# YarnControl_Driver_v1_3.net
KiCad netlist of a schematic drawn in Altium Designer
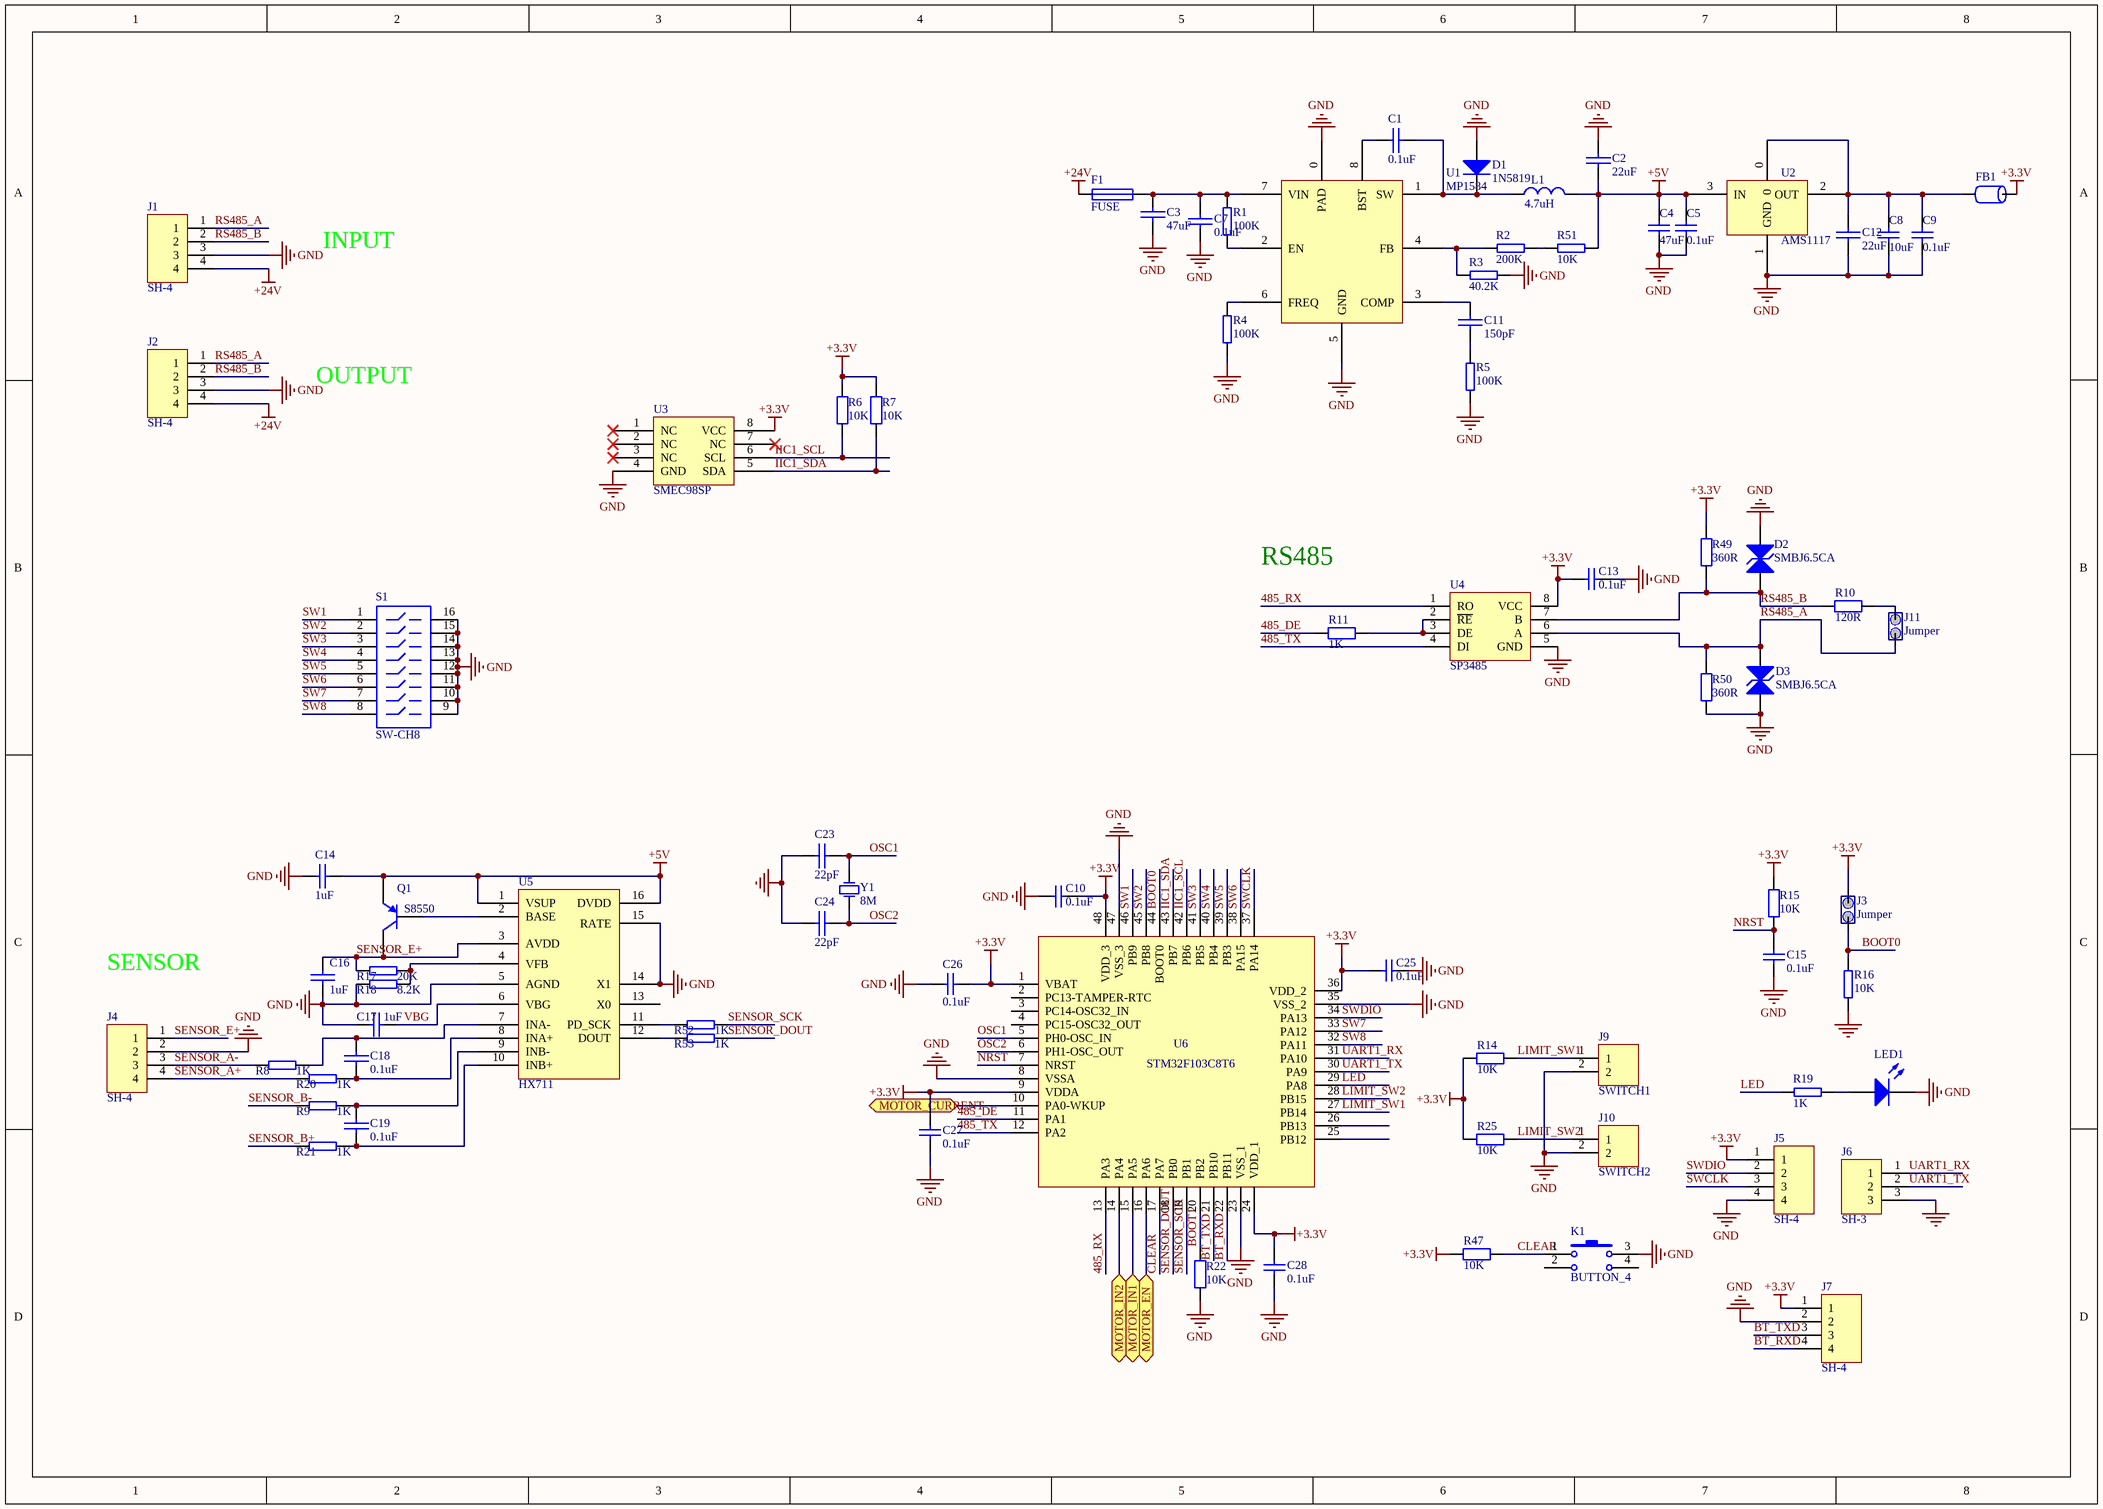
[diagram p0: YarnControl_Driver_v1.3.SchDoc]

(export (version "E")
  (design (tool "Eeschema 10.0.6"))
  (components
    (comp (ref "C1")
      (value "0.1uF")
      (footprint "0805")
      (description "电容")
      (libsource (lib "Component") (part "CAP"))
    )
    (comp (ref "C2")
      (value "22uF")
      (footprint "1206")
      (description "电容")
      (libsource (lib "Component") (part "CAP"))
    )
    (comp (ref "C3")
      (value "47uF")
      (footprint "1812")
      (description "电容")
      (libsource (lib "Component") (part "CAP"))
    )
    (comp (ref "C4") (value "47uF") (footprint "1210") (libsource (lib "Componet") (part "Cap0805")))
    (comp (ref "C5") (value "0.1uF") (footprint "0805") (libsource (lib "Componet") (part "Cap0805")))
    (comp (ref "C7")
      (value "0.1uF")
      (footprint "0805")
      (description "电容")
      (libsource (lib "Component") (part "CAP"))
    )
    (comp (ref "C8") (value "10uF") (footprint "0805") (libsource (lib "Componet") (part "Cap0805")))
    (comp (ref "C9") (value "0.1uF") (footprint "0805") (libsource (lib "Componet") (part "Cap0805")))
    (comp (ref "C10")
      (value "0.1uF")
      (footprint "0805")
      (description "Capacitor")
      (fields (field (name "PUBLISHER") "Altium Limited"))
      (libsource (lib "TIAN's Schlib") (part "Cap"))
    )
    (comp (ref "C11")
      (value "150pF")
      (footprint "0805")
      (description "电容")
      (libsource (lib "Component") (part "CAP"))
    )
    (comp (ref "C12")
      (value "22uF")
      (footprint "1206")
      (description "电容")
      (libsource (lib "Component") (part "CAP"))
    )
    (comp (ref "C13")
      (value "0.1uF")
      (footprint "0805")
      (description "Capacitor")
      (fields (field (name "PUBLISHER") "Altium Limited"))
      (libsource (lib "TIAN's Schlib") (part "Cap"))
    )
    (comp (ref "C14")
      (value "1uF")
      (footprint "0805")
      (description "电容")
      (libsource (lib "Component") (part "CAP"))
    )
    (comp (ref "C15")
      (value "0.1uF")
      (footprint "0805")
      (description "Capacitor")
      (fields (field (name "PUBLISHER") "Altium Limited"))
      (libsource (lib "TIAN's Schlib") (part "Cap"))
    )
    (comp (ref "C16")
      (value "1uF")
      (footprint "0805")
      (description "电容")
      (libsource (lib "Component") (part "CAP"))
    )
    (comp (ref "C17")
      (value "1uF")
      (footprint "0805")
      (description "电容")
      (libsource (lib "Component") (part "CAP"))
    )
    (comp (ref "C18")
      (value "0.1uF")
      (footprint "0805")
      (description "电容")
      (libsource (lib "Component") (part "CAP"))
    )
    (comp (ref "C19")
      (value "0.1uF")
      (footprint "0805")
      (description "电容")
      (libsource (lib "Component") (part "CAP"))
    )
    (comp (ref "C23")
      (value "22pF")
      (footprint "0805")
      (description "电容")
      (libsource (lib "Component") (part "CAP"))
    )
    (comp (ref "C24")
      (value "22pF")
      (footprint "0805")
      (description "电容")
      (libsource (lib "Component") (part "CAP"))
    )
    (comp (ref "C25")
      (value "0.1uF")
      (footprint "0805")
      (description "Capacitor")
      (fields (field (name "PUBLISHER") "Altium Limited"))
      (libsource (lib "TIAN's Schlib") (part "Cap"))
    )
    (comp (ref "C26")
      (value "0.1uF")
      (footprint "0805")
      (description "Capacitor")
      (fields (field (name "PUBLISHER") "Altium Limited"))
      (libsource (lib "TIAN's Schlib") (part "Cap"))
    )
    (comp (ref "C27")
      (value "0.1uF")
      (footprint "0805")
      (description "Capacitor")
      (fields (field (name "PUBLISHER") "Altium Limited"))
      (libsource (lib "TIAN's Schlib") (part "Cap"))
    )
    (comp (ref "C28")
      (value "0.1uF")
      (footprint "0805")
      (description "Capacitor")
      (fields (field (name "PUBLISHER") "Altium Limited"))
      (libsource (lib "TIAN's Schlib") (part "Cap"))
    )
    (comp (ref "D1")
      (value "1N5819")
      (footprint "Diode_TP2")
      (description "二极管")
      (fields (field (name "PUBLISHER") "Altium Limited"))
      (libsource (lib "Component") (part "Diode"))
    )
    (comp (ref "D2")
      (value "SMBJ6.5CA")
      (footprint "SMBJ_DO-214")
      (fields (field (name "PUBLISHER") "Altium Limited"))
      (libsource (lib "TIAN's Schlib") (part "TVS"))
    )
    (comp (ref "D3")
      (value "SMBJ6.5CA")
      (footprint "SMBJ_DO-214")
      (fields (field (name "PUBLISHER") "Altium Limited"))
      (libsource (lib "TIAN's Schlib") (part "TVS"))
    )
    (comp (ref "F1")
      (value "FUSE")
      (footprint "1206")
      (description "保险丝")
      (libsource (lib "Component") (part "FUSE"))
    )
    (comp (ref "FB1") (value "FERRITE") (footprint "0805") (libsource (lib "Connector") (part "FERRITE")))
    (comp (ref "J1") (value "SH-4") (footprint "J381-4-90") (libsource (lib "") (part "SH-4_1")))
    (comp (ref "J2") (value "SH-4") (footprint "J381-4-90") (libsource (lib "") (part "SH-4_1")))
    (comp (ref "J3") (value "Jumper") (footprint "J254-2") (libsource (lib "Connector") (part "Jumper")))
    (comp (ref "J4") (value "SH-4") (footprint "KF2510-4") (libsource (lib "") (part "SH-4_1")))
    (comp (ref "J5") (value "SH-4") (footprint "J254-4") (libsource (lib "Connector") (part "SH-4")))
    (comp (ref "J6") (value "SH-3") (footprint "J2.54-3") (libsource (lib "Connector") (part "SH-3")))
    (comp (ref "J7") (value "SH-4") (footprint "J254-4") (libsource (lib "Connector") (part "SH-4")))
    (comp (ref "J9") (value "SWITCH1") (footprint "XH2.54-2T") (libsource (lib "Connector") (part "SH-2")))
    (comp (ref "J10") (value "SWITCH2") (footprint "XH2.54-2T") (libsource (lib "Connector") (part "SH-2")))
    (comp (ref "J11") (value "Jumper") (footprint "J254-2") (libsource (lib "Connector") (part "Jumper")))
    (comp (ref "K1") (value "BUTTON_4") (footprint "Button1") (libsource (lib "Componet") (part "BUTTON_4")))
    (comp (ref "L1")
      (value "4.7uH")
      (footprint "Inductance6*6")
      (description "电感")
      (libsource (lib "Component") (part "Inductor"))
    )
    (comp (ref "LED1")
      (value "GREEN")
      (footprint "LED")
      (description "Typical RED, GREEN, YELLOW, AMBER GaAs LED")
      (fields (field (name "PUBLISHER") "Altium Limited"))
      (libsource (lib "Miscellaneous Devices") (part "LED2"))
    )
    (comp (ref "Q1") (value "S8550") (footprint "901X_SOT-23") (libsource (lib "Componet") (part "PNP")))
    (comp (ref "R1")
      (value "100K")
      (footprint "0805")
      (description "电阻")
      (libsource (lib "Component") (part "RES"))
    )
    (comp (ref "R2")
      (value "200K")
      (footprint "0805")
      (description "电阻")
      (libsource (lib "Component") (part "RES"))
    )
    (comp (ref "R3")
      (value "40.2K")
      (footprint "0805")
      (description "电阻")
      (libsource (lib "Component") (part "RES"))
    )
    (comp (ref "R4")
      (value "100K")
      (footprint "0805")
      (description "电阻")
      (libsource (lib "Component") (part "RES"))
    )
    (comp (ref "R5")
      (value "100K")
      (footprint "0805")
      (description "电阻")
      (libsource (lib "Component") (part "RES"))
    )
    (comp (ref "R6")
      (value "10K")
      (footprint "0805")
      (description "Resistor")
      (fields (field (name "PUBLISHER") "Altium Limited"))
      (libsource (lib "") (part "Res2_2"))
    )
    (comp (ref "R7")
      (value "10K")
      (footprint "0805")
      (description "Resistor")
      (fields (field (name "PUBLISHER") "Altium Limited"))
      (libsource (lib "") (part "Res2_2"))
    )
    (comp (ref "R8")
      (value "1K")
      (footprint "0805")
      (description "电阻")
      (libsource (lib "Component") (part "RES"))
    )
    (comp (ref "R9")
      (value "1K")
      (footprint "0805")
      (description "电阻")
      (libsource (lib "Component") (part "RES"))
    )
    (comp (ref "R10")
      (value "120R")
      (footprint "0805")
      (description "Resistor")
      (fields (field (name "PUBLISHER") "Altium Limited"))
      (libsource (lib "TIAN's Schlib") (part "Res2"))
    )
    (comp (ref "R11")
      (value "1K")
      (footprint "0805")
      (description "Resistor")
      (fields (field (name "PUBLISHER") "Altium Limited"))
      (libsource (lib "") (part "Res2_1"))
    )
    (comp (ref "R14")
      (value "10K")
      (footprint "0805")
      (description "Resistor")
      (fields (field (name "PUBLISHER") "Altium Limited"))
      (libsource (lib "") (part "Res2_1"))
    )
    (comp (ref "R15")
      (value "10K")
      (footprint "0805")
      (description "Resistor")
      (fields (field (name "PUBLISHER") "Altium Limited"))
      (libsource (lib "") (part "Res2_2"))
    )
    (comp (ref "R16")
      (value "10K")
      (footprint "0805")
      (description "电阻")
      (libsource (lib "Component") (part "RES"))
    )
    (comp (ref "R17")
      (value "20K")
      (footprint "0805")
      (description "电阻")
      (libsource (lib "Component") (part "RES"))
    )
    (comp (ref "R18")
      (value "8.2K")
      (footprint "0805")
      (description "电阻")
      (libsource (lib "Component") (part "RES"))
    )
    (comp (ref "R19")
      (value "1K")
      (footprint "0805")
      (description "电阻")
      (libsource (lib "Component") (part "RES"))
    )
    (comp (ref "R20")
      (value "1K")
      (footprint "0805")
      (description "电阻")
      (libsource (lib "Component") (part "RES"))
    )
    (comp (ref "R21")
      (value "1K")
      (footprint "0805")
      (description "电阻")
      (libsource (lib "Component") (part "RES"))
    )
    (comp (ref "R22")
      (value "10K")
      (footprint "0805")
      (description "Resistor")
      (fields (field (name "PUBLISHER") "Altium Limited"))
      (libsource (lib "") (part "Res2_2"))
    )
    (comp (ref "R25")
      (value "10K")
      (footprint "0805")
      (description "Resistor")
      (fields (field (name "PUBLISHER") "Altium Limited"))
      (libsource (lib "TIAN's Schlib") (part "Res2"))
    )
    (comp (ref "R47")
      (value "10K")
      (footprint "0805")
      (description "Resistor")
      (fields (field (name "PUBLISHER") "Altium Limited"))
      (libsource (lib "TIAN's Schlib") (part "Res2"))
    )
    (comp (ref "R49")
      (value "360R")
      (footprint "0805")
      (description "Resistor")
      (fields (field (name "PUBLISHER") "Altium Limited"))
      (libsource (lib "TIAN's Schlib") (part "Res2"))
    )
    (comp (ref "R50")
      (value "360R")
      (footprint "0805")
      (description "Resistor")
      (fields (field (name "PUBLISHER") "Altium Limited"))
      (libsource (lib "TIAN's Schlib") (part "Res2"))
    )
    (comp (ref "R51")
      (value "10K")
      (footprint "0805")
      (description "电阻")
      (libsource (lib "Component") (part "RES"))
    )
    (comp (ref "R52")
      (value "1K")
      (footprint "0805")
      (description "电阻")
      (libsource (lib "Component") (part "RES"))
    )
    (comp (ref "R53")
      (value "1K")
      (footprint "0805")
      (description "电阻")
      (libsource (lib "Component") (part "RES"))
    )
    (comp (ref "S1")
      (value "SW-CH8")
      (footprint "SWITCH_8")
      (description "拨码开关CH8")
      (fields (field (name "PUBLISHER") "Altium Limited"))
      (libsource (lib "Component") (part "SW-CH8"))
    )
    (comp (ref "U1") (value "MP1584") (footprint "MP1584") (libsource (lib "Chip") (part "MP1584")))
    (comp (ref "U2") (value "AMS1117") (footprint "TO-223") (libsource (lib "Chip") (part "AMS1117")))
    (comp (ref "U3") (value "SMEC98SP") (footprint "SO-8") (libsource (lib "Chip") (part "SMEC98SP")))
    (comp (ref "U4")
      (value "SP3485")
      (footprint "SO-8")
      (description "485")
      (libsource (lib "TIAN's Schlib") (part "SP3485"))
    )
    (comp (ref "U5") (value "HX711") (footprint "SO-16") (libsource (lib "Chip") (part "HX711")))
    (comp (ref "U6")
      (value "STM32F103C8T6")
      (footprint "LQFP_48")
      (libsource (lib "Chip") (part "STM32F103C8T6"))
    )
    (comp (ref "Y1")
      (value "8M")
      (footprint "XTAL")
      (description "Crystal Oscillator")
      (fields (field (name "PUBLISHER") "Altium Limited"))
      (libsource (lib "MY Schlib") (part "XTAL"))
    )
  )
  (nets
    (net (code "1") (name "+3.3V") (class "Default")
      (node (ref "C10") (pin "1") (pinfunction "1_1") (pintype "passive"))
      (node (ref "C13") (pin "2") (pinfunction "2_2") (pintype "passive"))
      (node (ref "C25") (pin "2") (pinfunction "2_2") (pintype "passive"))
      (node (ref "C26") (pin "2") (pinfunction "2_2") (pintype "passive"))
      (node (ref "C27") (pin "2") (pinfunction "2_2") (pintype "passive"))
      (node (ref "C28") (pin "2") (pinfunction "2_2") (pintype "passive"))
      (node (ref "FB1") (pin "2") (pinfunction "2_2") (pintype "passive"))
      (node (ref "J3") (pin "2") (pinfunction "2_2") (pintype "passive"))
      (node (ref "J5") (pin "1") (pinfunction "1_1") (pintype "passive"))
      (node (ref "J7") (pin "1") (pinfunction "1_1") (pintype "passive"))
      (node (ref "R14") (pin "2") (pinfunction "2_2") (pintype "passive"))
      (node (ref "R15") (pin "2") (pinfunction "2_2") (pintype "passive"))
      (node (ref "R25") (pin "1") (pinfunction "1_1") (pintype "passive"))
      (node (ref "R47") (pin "1") (pinfunction "1_1") (pintype "passive"))
      (node (ref "R49") (pin "2") (pinfunction "2_2") (pintype "passive"))
      (node (ref "R6") (pin "2") (pinfunction "2_2") (pintype "passive"))
      (node (ref "R7") (pin "2") (pinfunction "2_2") (pintype "passive"))
      (node (ref "U3") (pin "8") (pinfunction "VCC_8") (pintype "passive"))
      (node (ref "U4") (pin "8") (pinfunction "VCC_8") (pintype "passive"))
      (node (ref "U6") (pin "1") (pinfunction "VBAT_1") (pintype "passive"))
      (node (ref "U6") (pin "24") (pinfunction "VDD_1_24") (pintype "passive"))
      (node (ref "U6") (pin "36") (pinfunction "VDD_2_36") (pintype "passive"))
      (node (ref "U6") (pin "48") (pinfunction "VDD_3_48") (pintype "passive"))
      (node (ref "U6") (pin "9") (pinfunction "VDDA_9") (pintype "passive"))
    )
    (net (code "2") (name "+5V") (class "Default")
      (node (ref "C14") (pin "2") (pinfunction "2_2") (pintype "passive"))
      (node (ref "C2") (pin "2") (pinfunction "2_2") (pintype "passive"))
      (node (ref "C4") (pin "2") (pinfunction "2_2") (pintype "passive"))
      (node (ref "C5") (pin "2") (pinfunction "2_2") (pintype "passive"))
      (node (ref "L1") (pin "2") (pinfunction "2_2") (pintype "passive"))
      (node (ref "Q1") (pin "3") (pinfunction "E_3") (pintype "passive"))
      (node (ref "R51") (pin "1") (pinfunction "1_1") (pintype "passive"))
      (node (ref "U2") (pin "3") (pinfunction "IN_3") (pintype "passive"))
      (node (ref "U5") (pin "1") (pinfunction "VSUP_1") (pintype "passive"))
      (node (ref "U5") (pin "16") (pinfunction "DVDD_16") (pintype "passive"))
    )
    (net (code "3") (name "+24V") (class "Default")
      (node (ref "F1") (pin "1") (pinfunction "1_1") (pintype "passive"))
      (node (ref "J1") (pin "4") (pinfunction "4_4") (pintype "passive"))
      (node (ref "J2") (pin "4") (pinfunction "4_4") (pintype "passive"))
    )
    (net (code "4") (name "/485_DE") (class "Default")
      (node (ref "R11") (pin "2") (pinfunction "2_2") (pintype "passive"))
      (node (ref "U6") (pin "11") (pinfunction "PA1_11") (pintype "passive"))
    )
    (net (code "5") (name "/485_RX") (class "Default")
      (node (ref "U4") (pin "1") (pinfunction "RO_1") (pintype "passive"))
      (node (ref "U6") (pin "13") (pinfunction "PA3_13") (pintype "passive"))
    )
    (net (code "6") (name "/485_TX") (class "Default")
      (node (ref "U4") (pin "4") (pinfunction "DI_4") (pintype "passive"))
      (node (ref "U6") (pin "12") (pinfunction "PA2_12") (pintype "passive"))
    )
    (net (code "7") (name "/BOOT0") (class "Default")
      (node (ref "J3") (pin "1") (pinfunction "1_1") (pintype "passive"))
      (node (ref "R16") (pin "1") (pinfunction "1_1") (pintype "passive"))
      (node (ref "U6") (pin "44") (pinfunction "BOOT0_44") (pintype "passive"))
    )
    (net (code "8") (name "/BOOT1") (class "Default")
      (node (ref "R22") (pin "2") (pinfunction "2_2") (pintype "passive"))
      (node (ref "U6") (pin "20") (pinfunction "PB2_20") (pintype "passive"))
    )
    (net (code "9") (name "/BT_RXD") (class "Default")
      (node (ref "J7") (pin "4") (pinfunction "4_4") (pintype "passive"))
      (node (ref "U6") (pin "22") (pinfunction "PB11_22") (pintype "passive"))
    )
    (net (code "10") (name "/BT_TXD") (class "Default")
      (node (ref "J7") (pin "3") (pinfunction "3_3") (pintype "passive"))
      (node (ref "U6") (pin "21") (pinfunction "PB10_21") (pintype "passive"))
    )
    (net (code "11") (name "/CLEAR") (class "Default")
      (node (ref "K1") (pin "1") (pinfunction "1_1") (pintype "passive"))
      (node (ref "R47") (pin "2") (pinfunction "2_2") (pintype "passive"))
      (node (ref "U6") (pin "17") (pinfunction "PA7_17") (pintype "passive"))
    )
    (net (code "12") (name "/IIC1_SCL") (class "Default")
      (node (ref "R6") (pin "1") (pinfunction "1_1") (pintype "passive"))
      (node (ref "U3") (pin "6") (pinfunction "SCL_6") (pintype "passive"))
      (node (ref "U6") (pin "42") (pinfunction "PB6_42") (pintype "passive"))
    )
    (net (code "13") (name "/IIC1_SDA") (class "Default")
      (node (ref "R7") (pin "1") (pinfunction "1_1") (pintype "passive"))
      (node (ref "U3") (pin "5") (pinfunction "SDA_5") (pintype "passive"))
      (node (ref "U6") (pin "43") (pinfunction "PB7_43") (pintype "passive"))
    )
    (net (code "14") (name "/LED") (class "Default")
      (node (ref "R19") (pin "2") (pinfunction "2_2") (pintype "passive"))
      (node (ref "U6") (pin "29") (pinfunction "PA8_29") (pintype "passive"))
    )
    (net (code "15") (name "/LIMIT_SW1") (class "Default")
      (node (ref "J9") (pin "1") (pinfunction "1_1") (pintype "passive"))
      (node (ref "R14") (pin "1") (pinfunction "1_1") (pintype "passive"))
      (node (ref "U6") (pin "27") (pinfunction "PB14_27") (pintype "passive"))
    )
    (net (code "16") (name "/LIMIT_SW2") (class "Default")
      (node (ref "J10") (pin "1") (pinfunction "1_1") (pintype "passive"))
      (node (ref "R25") (pin "2") (pinfunction "2_2") (pintype "passive"))
      (node (ref "U6") (pin "28") (pinfunction "PB15_28") (pintype "passive"))
    )
    (net (code "17") (name "/MOTOR_CURRENT") (class "Default")
      (node (ref "U6") (pin "10") (pinfunction "PA0-WKUP_10") (pintype "passive"))
    )
    (net (code "18") (name "/MOTOR_EN") (class "Default")
      (node (ref "U6") (pin "16") (pinfunction "PA6_16") (pintype "passive"))
    )
    (net (code "19") (name "/MOTOR_IN1") (class "Default")
      (node (ref "U6") (pin "15") (pinfunction "PA5_15") (pintype "passive"))
    )
    (net (code "20") (name "/MOTOR_IN2") (class "Default")
      (node (ref "U6") (pin "14") (pinfunction "PA4_14") (pintype "passive"))
    )
    (net (code "21") (name "/NRST") (class "Default")
      (node (ref "C15") (pin "2") (pinfunction "2_2") (pintype "passive"))
      (node (ref "R15") (pin "1") (pinfunction "1_1") (pintype "passive"))
      (node (ref "U6") (pin "7") (pinfunction "NRST_7") (pintype "passive"))
    )
    (net (code "22") (name "/OSC1") (class "Default")
      (node (ref "C23") (pin "2") (pinfunction "2_2") (pintype "passive"))
      (node (ref "U6") (pin "5") (pinfunction "PH0-OSC_IN_5") (pintype "passive"))
      (node (ref "Y1") (pin "2") (pinfunction "OSC2_2") (pintype "passive"))
    )
    (net (code "23") (name "/OSC2") (class "Default")
      (node (ref "C24") (pin "2") (pinfunction "2_2") (pintype "passive"))
      (node (ref "U6") (pin "6") (pinfunction "PH1-OSC_OUT_6") (pintype "passive"))
      (node (ref "Y1") (pin "1") (pinfunction "OSC1_1") (pintype "passive"))
    )
    (net (code "24") (name "/RS485_A") (class "Default")
      (node (ref "D3") (pin "2") (pinfunction "K_2") (pintype "passive"))
      (node (ref "J1") (pin "1") (pinfunction "1_1") (pintype "passive"))
      (node (ref "J11") (pin "1") (pinfunction "1_1") (pintype "passive"))
      (node (ref "J2") (pin "1") (pinfunction "1_1") (pintype "passive"))
      (node (ref "R50") (pin "2") (pinfunction "2_2") (pintype "passive"))
      (node (ref "U4") (pin "6") (pinfunction "A_6") (pintype "passive"))
    )
    (net (code "25") (name "/RS485_B") (class "Default")
      (node (ref "D2") (pin "1") (pinfunction "A_1") (pintype "passive"))
      (node (ref "J1") (pin "2") (pinfunction "2_2") (pintype "passive"))
      (node (ref "J2") (pin "2") (pinfunction "2_2") (pintype "passive"))
      (node (ref "R10") (pin "1") (pinfunction "1_1") (pintype "passive"))
      (node (ref "R49") (pin "1") (pinfunction "1_1") (pintype "passive"))
      (node (ref "U4") (pin "7") (pinfunction "B_7") (pintype "passive"))
    )
    (net (code "26") (name "/SENSOR_A+") (class "Default")
      (node (ref "J4") (pin "4") (pinfunction "4_4") (pintype "passive"))
      (node (ref "R20") (pin "2") (pinfunction "2_2") (pintype "passive"))
    )
    (net (code "27") (name "/SENSOR_A-") (class "Default")
      (node (ref "J4") (pin "3") (pinfunction "3_3") (pintype "passive"))
      (node (ref "R8") (pin "2") (pinfunction "2_2") (pintype "passive"))
    )
    (net (code "28") (name "/SENSOR_B+") (class "Default")
      (node (ref "R21") (pin "2") (pinfunction "2_2") (pintype "passive"))
    )
    (net (code "29") (name "/SENSOR_B-") (class "Default")
      (node (ref "R9") (pin "2") (pinfunction "2_2") (pintype "passive"))
    )
    (net (code "30") (name "/SENSOR_DOUT") (class "Default")
      (node (ref "R53") (pin "1") (pinfunction "1_1") (pintype "passive"))
      (node (ref "U6") (pin "18") (pinfunction "PB0_18") (pintype "passive"))
    )
    (net (code "31") (name "/SENSOR_E+") (class "Default")
      (node (ref "C16") (pin "2") (pinfunction "2_2") (pintype "passive"))
      (node (ref "J4") (pin "1") (pinfunction "1_1") (pintype "passive"))
      (node (ref "Q1") (pin "1") (pinfunction "C_1") (pintype "passive"))
      (node (ref "R17") (pin "2") (pinfunction "2_2") (pintype "passive"))
      (node (ref "U5") (pin "3") (pinfunction "AVDD_3") (pintype "passive"))
    )
    (net (code "32") (name "/SENSOR_SCK") (class "Default")
      (node (ref "R52") (pin "1") (pinfunction "1_1") (pintype "passive"))
      (node (ref "U6") (pin "19") (pinfunction "PB1_19") (pintype "passive"))
    )
    (net (code "33") (name "/SW1") (class "Default")
      (node (ref "S1") (pin "1") (pinfunction "1_1") (pintype "passive"))
      (node (ref "U6") (pin "46") (pinfunction "PB9_46") (pintype "passive"))
    )
    (net (code "34") (name "/SW2") (class "Default")
      (node (ref "S1") (pin "2") (pinfunction "2_2") (pintype "passive"))
      (node (ref "U6") (pin "45") (pinfunction "PB8_45") (pintype "passive"))
    )
    (net (code "35") (name "/SW3") (class "Default")
      (node (ref "S1") (pin "3") (pinfunction "3_3") (pintype "passive"))
      (node (ref "U6") (pin "41") (pinfunction "PB5_41") (pintype "passive"))
    )
    (net (code "36") (name "/SW4") (class "Default")
      (node (ref "S1") (pin "4") (pinfunction "4_4") (pintype "passive"))
      (node (ref "U6") (pin "40") (pinfunction "PB4_40") (pintype "passive"))
    )
    (net (code "37") (name "/SW5") (class "Default")
      (node (ref "S1") (pin "5") (pinfunction "5_5") (pintype "passive"))
      (node (ref "U6") (pin "39") (pinfunction "PB3_39") (pintype "passive"))
    )
    (net (code "38") (name "/SW6") (class "Default")
      (node (ref "S1") (pin "6") (pinfunction "6_6") (pintype "passive"))
      (node (ref "U6") (pin "38") (pinfunction "PA15_38") (pintype "passive"))
    )
    (net (code "39") (name "/SW7") (class "Default")
      (node (ref "S1") (pin "7") (pinfunction "7_7") (pintype "passive"))
      (node (ref "U6") (pin "33") (pinfunction "PA12_33") (pintype "passive"))
    )
    (net (code "40") (name "/SW8") (class "Default")
      (node (ref "S1") (pin "8") (pinfunction "8_8") (pintype "passive"))
      (node (ref "U6") (pin "32") (pinfunction "PA11_32") (pintype "passive"))
    )
    (net (code "41") (name "/SWCLK") (class "Default")
      (node (ref "J5") (pin "3") (pinfunction "3_3") (pintype "passive"))
      (node (ref "U6") (pin "37") (pinfunction "PA14_37") (pintype "passive"))
    )
    (net (code "42") (name "/SWDIO") (class "Default")
      (node (ref "J5") (pin "2") (pinfunction "2_2") (pintype "passive"))
      (node (ref "U6") (pin "34") (pinfunction "PA13_34") (pintype "passive"))
    )
    (net (code "43") (name "/UART1_RX") (class "Default")
      (node (ref "J6") (pin "1") (pinfunction "1_1") (pintype "passive"))
      (node (ref "U6") (pin "31") (pinfunction "PA10_31") (pintype "passive"))
    )
    (net (code "44") (name "/UART1_TX") (class "Default")
      (node (ref "J6") (pin "2") (pinfunction "2_2") (pintype "passive"))
      (node (ref "U6") (pin "30") (pinfunction "PA9_30") (pintype "passive"))
    )
    (net (code "45") (name "/VBG") (class "Default")
      (node (ref "C17") (pin "1") (pinfunction "1_1") (pintype "passive"))
      (node (ref "U5") (pin "6") (pinfunction "VBG_6") (pintype "passive"))
    )
    (net (code "46") (name "GND") (class "Default")
      (node (ref "C10") (pin "2") (pinfunction "2_2") (pintype "passive"))
      (node (ref "C12") (pin "2") (pinfunction "2_2") (pintype "passive"))
      (node (ref "C13") (pin "1") (pinfunction "1_1") (pintype "passive"))
      (node (ref "C14") (pin "1") (pinfunction "1_1") (pintype "passive"))
      (node (ref "C15") (pin "1") (pinfunction "1_1") (pintype "passive"))
      (node (ref "C16") (pin "1") (pinfunction "1_1") (pintype "passive"))
      (node (ref "C17") (pin "2") (pinfunction "2_2") (pintype "passive"))
      (node (ref "C2") (pin "1") (pinfunction "1_1") (pintype "passive"))
      (node (ref "C23") (pin "1") (pinfunction "1_1") (pintype "passive"))
      (node (ref "C24") (pin "1") (pinfunction "1_1") (pintype "passive"))
      (node (ref "C25") (pin "1") (pinfunction "1_1") (pintype "passive"))
      (node (ref "C26") (pin "1") (pinfunction "1_1") (pintype "passive"))
      (node (ref "C27") (pin "1") (pinfunction "1_1") (pintype "passive"))
      (node (ref "C28") (pin "1") (pinfunction "1_1") (pintype "passive"))
      (node (ref "C3") (pin "2") (pinfunction "2_2") (pintype "passive"))
      (node (ref "C4") (pin "1") (pinfunction "1_1") (pintype "passive"))
      (node (ref "C5") (pin "1") (pinfunction "1_1") (pintype "passive"))
      (node (ref "C7") (pin "2") (pinfunction "2_2") (pintype "passive"))
      (node (ref "C8") (pin "1") (pinfunction "1_1") (pintype "passive"))
      (node (ref "C9") (pin "1") (pinfunction "1_1") (pintype "passive"))
      (node (ref "D1") (pin "1") (pinfunction "A_1") (pintype "passive"))
      (node (ref "D2") (pin "2") (pinfunction "K_2") (pintype "passive"))
      (node (ref "D3") (pin "1") (pinfunction "A_1") (pintype "passive"))
      (node (ref "J1") (pin "3") (pinfunction "3_3") (pintype "passive"))
      (node (ref "J10") (pin "2") (pinfunction "2_2") (pintype "passive"))
      (node (ref "J2") (pin "3") (pinfunction "3_3") (pintype "passive"))
      (node (ref "J4") (pin "2") (pinfunction "2_2") (pintype "passive"))
      (node (ref "J5") (pin "4") (pinfunction "4_4") (pintype "passive"))
      (node (ref "J6") (pin "3") (pinfunction "3_3") (pintype "passive"))
      (node (ref "J7") (pin "2") (pinfunction "2_2") (pintype "passive"))
      (node (ref "J9") (pin "2") (pinfunction "2_2") (pintype "passive"))
      (node (ref "K1") (pin "3") (pinfunction "3_3") (pintype "passive"))
      (node (ref "LED1") (pin "2") (pinfunction "K_2") (pintype "passive"))
      (node (ref "R16") (pin "2") (pinfunction "2_2") (pintype "passive"))
      (node (ref "R18") (pin "2") (pinfunction "2_2") (pintype "passive"))
      (node (ref "R22") (pin "1") (pinfunction "1_1") (pintype "passive"))
      (node (ref "R3") (pin "1") (pinfunction "1_1") (pintype "passive"))
      (node (ref "R4") (pin "1") (pinfunction "1_1") (pintype "passive"))
      (node (ref "R5") (pin "1") (pinfunction "1_1") (pintype "passive"))
      (node (ref "R50") (pin "1") (pinfunction "1_1") (pintype "passive"))
      (node (ref "S1") (pin "10") (pinfunction "10_10") (pintype "passive"))
      (node (ref "S1") (pin "11") (pinfunction "11_11") (pintype "passive"))
      (node (ref "S1") (pin "12") (pinfunction "12_12") (pintype "passive"))
      (node (ref "S1") (pin "13") (pinfunction "13_13") (pintype "passive"))
      (node (ref "S1") (pin "14") (pinfunction "14_14") (pintype "passive"))
      (node (ref "S1") (pin "15") (pinfunction "15_15") (pintype "passive"))
      (node (ref "S1") (pin "16") (pinfunction "16_16") (pintype "passive"))
      (node (ref "S1") (pin "9") (pinfunction "9_9") (pintype "passive"))
      (node (ref "U1") (pin "0") (pinfunction "PAD_0") (pintype "passive"))
      (node (ref "U1") (pin "5") (pinfunction "GND_5") (pintype "passive"))
      (node (ref "U2") (pin "1") (pinfunction "GND_1") (pintype "passive"))
      (node (ref "U3") (pin "4") (pinfunction "GND_4") (pintype "passive"))
      (node (ref "U4") (pin "5") (pinfunction "GND_5") (pintype "passive"))
      (node (ref "U5") (pin "14") (pinfunction "X1_14") (pintype "passive"))
      (node (ref "U5") (pin "15") (pinfunction "RATE_15") (pintype "passive"))
      (node (ref "U5") (pin "5") (pinfunction "AGND_5") (pintype "passive"))
      (node (ref "U6") (pin "23") (pinfunction "VSS_1_23") (pintype "passive"))
      (node (ref "U6") (pin "35") (pinfunction "VSS_2_35") (pintype "passive"))
      (node (ref "U6") (pin "47") (pinfunction "VSS_3_47") (pintype "passive"))
      (node (ref "U6") (pin "8") (pinfunction "VSSA_8") (pintype "passive"))
    )
    (net (code "47") (name "Net-(C11-Pad2)") (class "Default")
      (node (ref "C11") (pin "2") (pinfunction "2_2") (pintype "passive"))
      (node (ref "R5") (pin "2") (pinfunction "2_2") (pintype "passive"))
    )
    (net (code "48") (name "Net-(D1-K)") (class "Default")
      (node (ref "C1") (pin "2") (pinfunction "2_2") (pintype "passive"))
      (node (ref "D1") (pin "2") (pinfunction "K_2") (pintype "passive"))
      (node (ref "L1") (pin "1") (pinfunction "1_1") (pintype "passive"))
      (node (ref "U1") (pin "1") (pinfunction "SW_1") (pintype "passive"))
    )
    (net (code "49") (name "Net-(J11-Pad2)") (class "Default")
      (node (ref "J11") (pin "2") (pinfunction "2_2") (pintype "passive"))
      (node (ref "R10") (pin "2") (pinfunction "2_2") (pintype "passive"))
    )
    (net (code "50") (name "Net-(LED1-A)") (class "Default")
      (node (ref "LED1") (pin "1") (pinfunction "A_1") (pintype "passive"))
      (node (ref "R19") (pin "1") (pinfunction "1_1") (pintype "passive"))
    )
    (net (code "51") (name "Net-(Q1-B)") (class "Default")
      (node (ref "Q1") (pin "2") (pinfunction "B_2") (pintype "passive"))
      (node (ref "U5") (pin "2") (pinfunction "BASE_2") (pintype "passive"))
    )
    (net (code "52") (name "Net-(R2-Pad1)") (class "Default")
      (node (ref "R2") (pin "1") (pinfunction "1_1") (pintype "passive"))
      (node (ref "R51") (pin "2") (pinfunction "2_2") (pintype "passive"))
    )
    (net (code "53") (name "Net-(U1-BST)") (class "Default")
      (node (ref "C1") (pin "1") (pinfunction "1_1") (pintype "passive"))
      (node (ref "U1") (pin "8") (pinfunction "BST_8") (pintype "passive"))
    )
    (net (code "54") (name "Net-(U1-COMP)") (class "Default")
      (node (ref "C11") (pin "1") (pinfunction "1_1") (pintype "passive"))
      (node (ref "U1") (pin "3") (pinfunction "COMP_3") (pintype "passive"))
    )
    (net (code "55") (name "Net-(U1-EN)") (class "Default")
      (node (ref "R1") (pin "1") (pinfunction "1_1") (pintype "passive"))
      (node (ref "U1") (pin "2") (pinfunction "EN_2") (pintype "passive"))
    )
    (net (code "56") (name "Net-(U1-FB)") (class "Default")
      (node (ref "R2") (pin "2") (pinfunction "2_2") (pintype "passive"))
      (node (ref "R3") (pin "2") (pinfunction "2_2") (pintype "passive"))
      (node (ref "U1") (pin "4") (pinfunction "FB_4") (pintype "passive"))
    )
    (net (code "57") (name "Net-(U1-FREQ)") (class "Default")
      (node (ref "R4") (pin "2") (pinfunction "2_2") (pintype "passive"))
      (node (ref "U1") (pin "6") (pinfunction "FREQ_6") (pintype "passive"))
    )
    (net (code "58") (name "Net-(U1-VIN)") (class "Default")
      (node (ref "C3") (pin "1") (pinfunction "1_1") (pintype "passive"))
      (node (ref "C7") (pin "1") (pinfunction "1_1") (pintype "passive"))
      (node (ref "F1") (pin "2") (pinfunction "2_2") (pintype "passive"))
      (node (ref "R1") (pin "2") (pinfunction "2_2") (pintype "passive"))
      (node (ref "U1") (pin "7") (pinfunction "VIN_7") (pintype "passive"))
    )
    (net (code "59") (name "Net-(U2-OUT)") (class "Default")
      (node (ref "C12") (pin "1") (pinfunction "1_1") (pintype "passive"))
      (node (ref "C8") (pin "2") (pinfunction "2_2") (pintype "passive"))
      (node (ref "C9") (pin "2") (pinfunction "2_2") (pintype "passive"))
      (node (ref "FB1") (pin "1") (pinfunction "1_1") (pintype "passive"))
      (node (ref "U2") (pin "0") (pinfunction "0_0") (pintype "passive"))
      (node (ref "U2") (pin "2") (pinfunction "OUT_2") (pintype "passive"))
    )
    (net (code "60") (name "Net-(U4-DE)") (class "Default")
      (node (ref "R11") (pin "1") (pinfunction "1_1") (pintype "passive"))
      (node (ref "U4") (pin "2") (pinfunction "~{RE}_2") (pintype "passive"))
      (node (ref "U4") (pin "3") (pinfunction "DE_3") (pintype "passive"))
    )
    (net (code "61") (name "Net-(U5-DOUT)") (class "Default")
      (node (ref "R53") (pin "2") (pinfunction "2_2") (pintype "passive"))
      (node (ref "U5") (pin "12") (pinfunction "DOUT_12") (pintype "passive"))
    )
    (net (code "62") (name "Net-(U5-INA+)") (class "Default")
      (node (ref "C18") (pin "2") (pinfunction "2_2") (pintype "passive"))
      (node (ref "R20") (pin "1") (pinfunction "1_1") (pintype "passive"))
      (node (ref "U5") (pin "8") (pinfunction "INA+_8") (pintype "passive"))
    )
    (net (code "63") (name "Net-(U5-INA-)") (class "Default")
      (node (ref "C18") (pin "1") (pinfunction "1_1") (pintype "passive"))
      (node (ref "R8") (pin "1") (pinfunction "1_1") (pintype "passive"))
      (node (ref "U5") (pin "7") (pinfunction "INA-_7") (pintype "passive"))
    )
    (net (code "64") (name "Net-(U5-INB+)") (class "Default")
      (node (ref "C19") (pin "2") (pinfunction "2_2") (pintype "passive"))
      (node (ref "R21") (pin "1") (pinfunction "1_1") (pintype "passive"))
      (node (ref "U5") (pin "10") (pinfunction "INB+_10") (pintype "passive"))
    )
    (net (code "65") (name "Net-(U5-INB-)") (class "Default")
      (node (ref "C19") (pin "1") (pinfunction "1_1") (pintype "passive"))
      (node (ref "R9") (pin "1") (pinfunction "1_1") (pintype "passive"))
      (node (ref "U5") (pin "9") (pinfunction "INB-_9") (pintype "passive"))
    )
    (net (code "66") (name "Net-(U5-PD_SCK)") (class "Default")
      (node (ref "R52") (pin "2") (pinfunction "2_2") (pintype "passive"))
      (node (ref "U5") (pin "11") (pinfunction "PD_SCK_11") (pintype "passive"))
    )
    (net (code "67") (name "Net-(U5-VFB)") (class "Default")
      (node (ref "R17") (pin "1") (pinfunction "1_1") (pintype "passive"))
      (node (ref "R18") (pin "1") (pinfunction "1_1") (pintype "passive"))
      (node (ref "U5") (pin "4") (pinfunction "VFB_4") (pintype "passive"))
    )
    (net (code "68") (name "unconnected-(K1-Pad2)") (class "Default")
      (node (ref "K1") (pin "2") (pinfunction "2_2") (pintype "passive"))
    )
    (net (code "69") (name "unconnected-(K1-Pad4)") (class "Default")
      (node (ref "K1") (pin "4") (pinfunction "4_4") (pintype "passive"))
    )
    (net (code "70") (name "unconnected-(U3-NC-Pad1)") (class "Default")
      (node (ref "U3") (pin "1") (pinfunction "NC_1") (pintype "passive+no_connect"))
    )
    (net (code "71") (name "unconnected-(U3-NC-Pad2)") (class "Default")
      (node (ref "U3") (pin "2") (pinfunction "NC_2") (pintype "passive+no_connect"))
    )
    (net (code "72") (name "unconnected-(U3-NC-Pad3)") (class "Default")
      (node (ref "U3") (pin "3") (pinfunction "NC_3") (pintype "passive+no_connect"))
    )
    (net (code "73") (name "unconnected-(U3-NC-Pad7)") (class "Default")
      (node (ref "U3") (pin "7") (pinfunction "NC_7") (pintype "passive+no_connect"))
    )
    (net (code "74") (name "unconnected-(U5-X0-Pad13)") (class "Default")
      (node (ref "U5") (pin "13") (pinfunction "X0_13") (pintype "passive"))
    )
    (net (code "75") (name "unconnected-(U6-PB12-Pad25)") (class "Default")
      (node (ref "U6") (pin "25") (pinfunction "PB12_25") (pintype "passive"))
    )
    (net (code "76") (name "unconnected-(U6-PB13-Pad26)") (class "Default")
      (node (ref "U6") (pin "26") (pinfunction "PB13_26") (pintype "passive"))
    )
    (net (code "77") (name "unconnected-(U6-PC13-TAMPER-RTC-Pad2)") (class "Default")
      (node (ref "U6") (pin "2") (pinfunction "PC13-TAMPER-RTC_2") (pintype "passive"))
    )
    (net (code "78") (name "unconnected-(U6-PC14-OSC32_IN-Pad3)") (class "Default")
      (node (ref "U6") (pin "3") (pinfunction "PC14-OSC32_IN_3") (pintype "passive"))
    )
    (net (code "79") (name "unconnected-(U6-PC15-OSC32_OUT-Pad4)") (class "Default")
      (node (ref "U6") (pin "4") (pinfunction "PC15-OSC32_OUT_4") (pintype "passive"))
    )
  )
)
